# 1117_Adj_SMD_0603.net
KiCad netlist of a schematic drawn in EAGLE
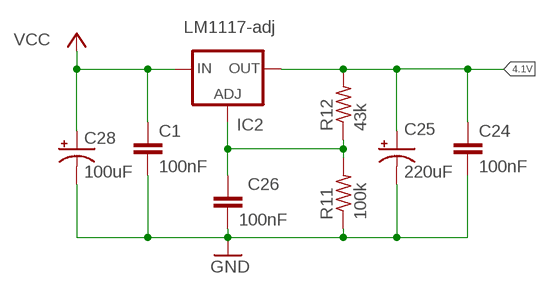
[diagram p0: schematic, sheet 1]

(export (version "E")
  (design (tool "Eeschema 10.0.6"))
  (components
    (comp (ref "C1")
      (value "100nF")
      (footprint "eagle-import:C0603")
      (libsource (lib "eagle-import") (part "C-EUC0603"))
    )
    (comp (ref "C24")
      (value "100nF")
      (footprint "eagle-import:C0603")
      (libsource (lib "eagle-import") (part "C-EUC0603"))
    )
    (comp (ref "C25")
      (value "220uF")
      (footprint "eagle-import:UD-6,3X7,7_NICHICON")
      (libsource (lib "eagle-import") (part "CPOL-USUD-6,3X7,7"))
    )
    (comp (ref "C26")
      (value "100nF")
      (footprint "eagle-import:C0603")
      (libsource (lib "eagle-import") (part "C-EUC0603"))
    )
    (comp (ref "C28")
      (value "100uF")
      (footprint "eagle-import:UD-6,3X7,7_NICHICON")
      (libsource (lib "eagle-import") (part "CPOL-USUD-6,3X7,7"))
    )
    (comp (ref "IC2")
      (value "LM1117-adj")
      (footprint "eagle-import:SOT223")
      (libsource (lib "eagle-import") (part "LD117A?S25TR"))
    )
    (comp (ref "R11")
      (value "100k")
      (footprint "eagle-import:R0603")
      (libsource (lib "eagle-import") (part "R-US_R0603"))
    )
    (comp (ref "R12")
      (value "43k")
      (footprint "eagle-import:R0603")
      (libsource (lib "eagle-import") (part "R-US_R0603"))
    )
  )
  (nets
    (net (code "1") (name "4.1V") (class "Default")
      (node (ref "C24") (pin "1") (pinfunction "1_1") (pintype "passive"))
      (node (ref "C25") (pin "+") (pinfunction "+_+") (pintype "passive"))
      (node (ref "IC2") (pin "4") (pinfunction "OUT_4") (pintype "passive"))
      (node (ref "R12") (pin "2") (pinfunction "2_2") (pintype "passive"))
    )
    (net (code "2") (name "GND") (class "Default")
      (node (ref "C1") (pin "2") (pinfunction "2_2") (pintype "passive"))
      (node (ref "C24") (pin "2") (pinfunction "2_2") (pintype "passive"))
      (node (ref "C25") (pin "-") (pinfunction "-_-") (pintype "passive"))
      (node (ref "C26") (pin "2") (pinfunction "2_2") (pintype "passive"))
      (node (ref "C28") (pin "-") (pinfunction "-_-") (pintype "passive"))
      (node (ref "R11") (pin "1") (pinfunction "1_1") (pintype "passive"))
    )
    (net (code "3") (name "Net-(IC2-ADJ)") (class "Default")
      (node (ref "C26") (pin "1") (pinfunction "1_1") (pintype "passive"))
      (node (ref "IC2") (pin "1") (pinfunction "ADJ_1") (pintype "input"))
      (node (ref "R11") (pin "2") (pinfunction "2_2") (pintype "passive"))
      (node (ref "R12") (pin "1") (pinfunction "1_1") (pintype "passive"))
    )
    (net (code "4") (name "VCC") (class "Default")
      (node (ref "C1") (pin "1") (pinfunction "1_1") (pintype "passive"))
      (node (ref "C28") (pin "+") (pinfunction "+_+") (pintype "passive"))
      (node (ref "IC2") (pin "3") (pinfunction "IN_3") (pintype "input"))
    )
  )
)
